# 05_NFC.net
KiCad netlist of a schematic drawn in Altium Designer
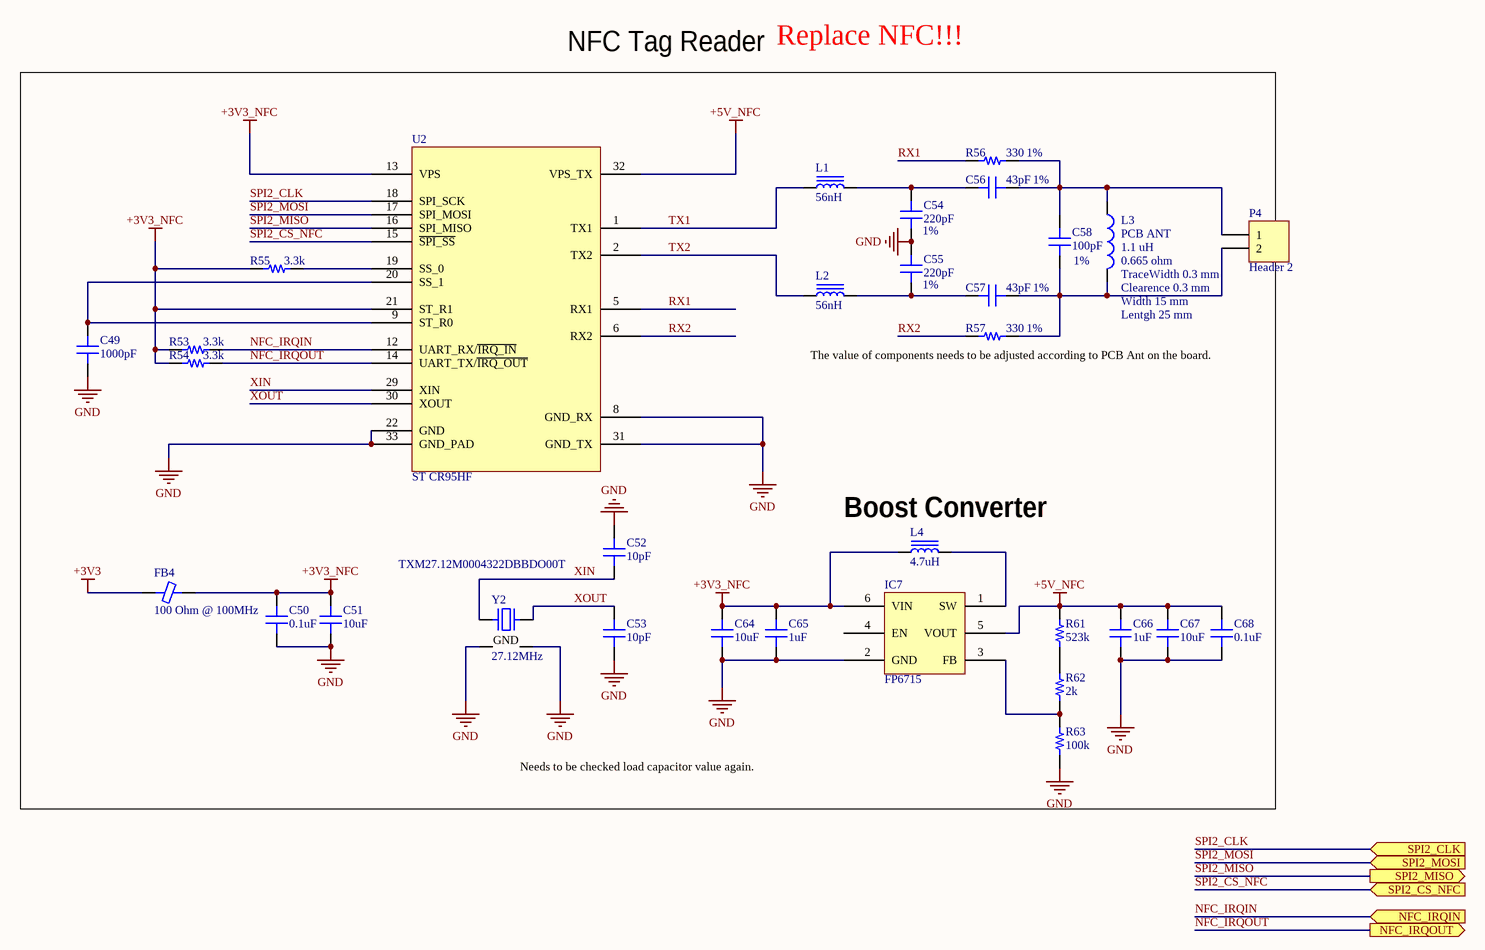
[diagram p0: [05] NFC.SchDoc]

(export (version "E")
  (design (tool "Eeschema 10.0.6"))
  (components
    (comp (ref "C49")
      (value "1000pF")
      (footprint "CAP 0402/1005")
      (description "CAP CER 1000PF 6.3V X7R 0402")
      (fields (field (name "PART NUMBER") "C0402C102K9RACTU") (field (name "MANUFACTURER") "Kemet"))
      (libsource (lib "Celestial Library Database") (part "Capacitor"))
    )
    (comp (ref "C50")
      (value "0.1uF")
      (footprint "CAP 0402/1005")
      (description "CAP CER 0.1UF 10V X7R 0402")
      (fields
        (field (name "PART NUMBER") "C1005X7R1A104K050BB")
        (field (name "MANUFACTURER") "TDK Corporation")
      )
      (libsource (lib "Celestial Library Database") (part "Capacitor"))
    )
    (comp (ref "C51")
      (value "10uF")
      (footprint "CAP 0603/1608")
      (description "CAP CER 10UF 10V X5R 0603")
      (fields
        (field (name "PART NUMBER") "C1608X5R1A106M080AC")
        (field (name "MANUFACTURER") "TDK Corporation")
      )
      (libsource (lib "Celestial Library Database") (part "Capacitor"))
    )
    (comp (ref "C52")
      (value "10pF")
      (footprint "CAP 0402/1005")
      (description "CAP CER 10PF 10V NP0 0402")
      (fields (field (name "PART NUMBER") "C0402C100C8GACTU") (field (name "MANUFACTURER") "Kemet"))
      (libsource (lib "Celestial Library Database") (part "Capacitor"))
    )
    (comp (ref "C53")
      (value "10pF")
      (footprint "CAP 0402/1005")
      (description "CAP CER 10PF 10V NP0 0402")
      (fields (field (name "PART NUMBER") "C0402C100C8GACTU") (field (name "MANUFACTURER") "Kemet"))
      (libsource (lib "Celestial Library Database") (part "Capacitor"))
    )
    (comp (ref "C54")
      (value "220pF")
      (footprint "CAP 0402/1005")
      (description "CAP CER 220PF 50V C0G 0402")
      (fields
        (field (name "PART NUMBER") "C1005C0G1H221F050BA")
        (field (name "MANUFACTURER") "TDK Corporation")
        (field (name "TOLERANCE") "1%")
      )
      (libsource (lib "Celestial Library Database") (part "Capacitor"))
    )
    (comp (ref "C55")
      (value "220pF")
      (footprint "CAP 0402/1005")
      (description "CAP CER 220PF 50V C0G 0402")
      (fields
        (field (name "PART NUMBER") "C1005C0G1H221F050BA")
        (field (name "MANUFACTURER") "TDK Corporation")
        (field (name "TOLERANCE") "1%")
      )
      (libsource (lib "Celestial Library Database") (part "Capacitor"))
    )
    (comp (ref "C56")
      (value "43pF")
      (footprint "CAP 0402/1005")
      (description "CAP CER 43PF 50V NP0 0402")
      (fields
        (field (name "PART NUMBER") "GRM1555C1H430GA01D")
        (field (name "MANUFACTURER") "Murata Electronics North America")
        (field (name "TOLERANCE") "1%")
      )
      (libsource (lib "Celestial Library Database") (part "Capacitor"))
    )
    (comp (ref "C57")
      (value "43pF")
      (footprint "CAP 0402/1005")
      (description "CAP CER 43PF 50V NP0 0402")
      (fields
        (field (name "PART NUMBER") "GRM1555C1H430GA01D")
        (field (name "MANUFACTURER") "Murata Electronics North America")
        (field (name "TOLERANCE") "1%")
      )
      (libsource (lib "Celestial Library Database") (part "Capacitor"))
    )
    (comp (ref "C58")
      (value "100pF")
      (footprint "CAP 0402/1005")
      (description "CAP CER 100PF 50V C0G 0402")
      (fields
        (field (name "PART NUMBER") "C1005C0G1H101F050BA")
        (field (name "MANUFACTURER") "TDK Corporation")
        (field (name "TOLERANCE") "1%")
      )
      (libsource (lib "Celestial Library Database") (part "Capacitor"))
    )
    (comp (ref "C64")
      (value "10uF")
      (footprint "CAP 0603/1608")
      (description "CAP CER 10UF 10V X5R 0603")
      (fields
        (field (name "PART NUMBER") "C1608X5R1A106K080AC")
        (field (name "MANUFACTURER") "TDK Corporation")
      )
      (libsource (lib "Celestial Library Database") (part "Capacitor"))
    )
    (comp (ref "C65")
      (value "1uF")
      (footprint "CAP 0603/1608")
      (description "CAP CER 1UF 25V X7R 0603")
      (fields (field (name "PART NUMBER") "C0603C105K3RACTU") (field (name "MANUFACTURER") "Kemet"))
      (libsource (lib "Celestial Library Database") (part "Capacitor"))
    )
    (comp (ref "C66")
      (value "1uF")
      (footprint "CAP 0603/1608")
      (description "CAP CER 1UF 25V X7R 0603")
      (fields (field (name "PART NUMBER") "C0603C105K3RACTU") (field (name "MANUFACTURER") "Kemet"))
      (libsource (lib "Celestial Library Database") (part "Capacitor"))
    )
    (comp (ref "C67")
      (value "10uF")
      (footprint "CAP 0603/1608")
      (description "CAP CER 10UF 10V X5R 0603")
      (fields
        (field (name "PART NUMBER") "C1608X5R1A106M080AC")
        (field (name "MANUFACTURER") "TDK Corporation")
      )
      (libsource (lib "Celestial Library Database") (part "Capacitor"))
    )
    (comp (ref "C68")
      (value "0.1uF")
      (footprint "CAP 0402/1005")
      (description "CAP CER 0.1UF 10V X7R 0402")
      (fields
        (field (name "PART NUMBER") "C1005X7R1A104K050BB")
        (field (name "MANUFACTURER") "TDK Corporation")
      )
      (libsource (lib "Celestial Library Database") (part "Capacitor"))
    )
    (comp (ref "FB4")
      (value "100 Ohm @ 100MHz")
      (footprint "FER 0603/1608")
      (description "FERRITE CHIP 100 OHM 0603")
      (fields (field (name "PART NUMBER") "BKP1608HS101-T") (field (name "MANUFACTURER") "Taiyo Yuden"))
      (libsource (lib "Celestial Library Database") (part "Ferrite Chip"))
    )
    (comp (ref "IC7")
      (value "FP6715")
      (footprint "Leaded:ATMEL SOT-23-6 6ST1")
      (description "550KHz High Efficiency Low Ripple Synchronous Step-Up Converter")
      (libsource (lib "Altium Component") (part "FP6715"))
    )
    (comp (ref "L1")
      (value "56nH")
      (footprint "IND 0402/1005 RF WW")
      (description "FIXED IND 56NH 200MA 1.17 OHM")
      (fields
        (field (name "PART NUMBER") "LQW15AN56NG00D")
        (field (name "MANUFACTURER") "Murata Electronics North America")
      )
      (libsource (lib "Celestial Library Database") (part "Inductor"))
    )
    (comp (ref "L2")
      (value "56nH")
      (footprint "IND 0402/1005 RF WW")
      (description "FIXED IND 56NH 200MA 1.17 OHM")
      (fields
        (field (name "PART NUMBER") "LQW15AN56NG00D")
        (field (name "MANUFACTURER") "Murata Electronics North America")
      )
      (libsource (lib "Celestial Library Database") (part "Inductor"))
    )
    (comp (ref "L3")
      (value "PCB ANT")
      (footprint "0402-A")
      (description "Inductor")
      (fields
        (field (name "L_ANT") "1.1 uH")
        (field (name "R_ANT") "0.665 ohm")
        (field (name "TRACEWIDTH") "TraceWidth 0.3 mm")
        (field (name "CLEARENCE") "Clearence 0.3 mm")
        (field (name "WIDTH") "Width 15 mm")
        (field (name "LENGTH") "Lentgh 25 mm")
        (field (name "PUBLISHER") "Altium Limited")
      )
      (libsource (lib "Miscellaneous Devices") (part "Inductor"))
    )
    (comp (ref "L4")
      (value "4.7uH")
      (footprint "TDK SPM3012")
      (description "FIXED IND 4.7UH 1.3A 270 MOHM")
      (fields (field (name "PART NUMBER") "SPM3012T-4R7M") (field (name "MANUFACTURER") "TDK Corporation"))
      (libsource (lib "Celestial Library Database") (part "Inductor"))
    )
    (comp (ref "P4")
      (value "Header 2")
      (footprint "HDR1X2")
      (description "Header, 2-Pin")
      (fields (field (name "PUBLISHER") "Altium Limited"))
      (libsource (lib "Miscellaneous Connectors") (part "Header 2"))
    )
    (comp (ref "R53")
      (value "3.3k")
      (footprint "RES 0402/1005")
      (description "RES SMD 3.3K OHM 5% 1/16W 0402")
      (fields (field (name "PART NUMBER") "RC0402JR-073K3L") (field (name "MANUFACTURER") "Yageo"))
      (libsource (lib "Celestial Library Database") (part "Resistor"))
    )
    (comp (ref "R54")
      (value "3.3k")
      (footprint "RES 0402/1005")
      (description "RES SMD 3.3K OHM 5% 1/16W 0402")
      (fields (field (name "PART NUMBER") "RC0402JR-073K3L") (field (name "MANUFACTURER") "Yageo"))
      (libsource (lib "Celestial Library Database") (part "Resistor"))
    )
    (comp (ref "R55")
      (value "3.3k")
      (footprint "RES 0402/1005")
      (description "RES SMD 3.3K OHM 5% 1/16W 0402")
      (fields (field (name "PART NUMBER") "RC0402JR-073K3L") (field (name "MANUFACTURER") "Yageo"))
      (libsource (lib "Celestial Library Database") (part "Resistor"))
    )
    (comp (ref "R56")
      (value "330")
      (footprint "RES 0402/1005")
      (description "RES SMD 330 OHM 1% 1/10W 0402")
      (fields
        (field (name "PART NUMBER") "ERJ-2RKF3300X")
        (field (name "MANUFACTURER") "Panasonic Electronic Components")
        (field (name "TOLERANCE") "1%")
      )
      (libsource (lib "Celestial Library Database") (part "Resistor"))
    )
    (comp (ref "R57")
      (value "330")
      (footprint "RES 0402/1005")
      (description "RES SMD 330 OHM 1% 1/10W 0402")
      (fields
        (field (name "PART NUMBER") "ERJ-2RKF3300X")
        (field (name "MANUFACTURER") "Panasonic Electronic Components")
        (field (name "TOLERANCE") "1%")
      )
      (libsource (lib "Celestial Library Database") (part "Resistor"))
    )
    (comp (ref "R61")
      (value "523k")
      (footprint "RES 0402/1005")
      (description "RES SMD 523K OHM 1% 1/10W 0402")
      (fields
        (field (name "PART NUMBER") "ERJ-2RKF5233X")
        (field (name "MANUFACTURER") "Panasonic Electronic Components")
      )
      (libsource (lib "Celestial Library Database") (part "Resistor"))
    )
    (comp (ref "R62")
      (value "2k")
      (footprint "RES 0402/1005")
      (description "RES SMD 2K OHM 5% 1/10W 0402")
      (fields
        (field (name "PART NUMBER") "ERJ-2GEJ202X")
        (field (name "MANUFACTURER") "Panasonic Electronic Components")
      )
      (libsource (lib "Celestial Library Database") (part "Resistor"))
    )
    (comp (ref "R63")
      (value "100k")
      (footprint "RES 0402/1005")
      (description "RES SMD 100K OHM 1% 1/10W 0402")
      (fields
        (field (name "PART NUMBER") "ERJ-2RKF1003X")
        (field (name "MANUFACTURER") "Panasonic Electronic Components")
      )
      (libsource (lib "Celestial Library Database") (part "Resistor"))
    )
    (comp (ref "U2")
      (value "ST CR95HF")
      (footprint "Leadless:ST VFQFPN-32")
      (libsource (lib "Altium Component") (part "ST CR95HF"))
    )
    (comp (ref "Y2")
      (value "27.12MHz")
      (footprint "NDK NX3225SA")
      (description "CRYSTAL 27.1200MHZ 8PF SMD")
      (fields (field (name "PART NUMBER") "TXM27.12M0004322DBBDO00T") (field (name "MANUFACTURER") "NDK"))
      (libsource (lib "Celestial Library Database") (part "NDK Crystal NX3225SA"))
    )
  )
  (nets
    (net (code "1") (name "+3V3") (class "Default")
      (node (ref "FB4") (pin "1") (pinfunction "1_1") (pintype "passive"))
    )
    (net (code "2") (name "+3V3_NFC") (class "Default")
      (node (ref "C50") (pin "2") (pinfunction "2_2") (pintype "passive"))
      (node (ref "C51") (pin "2") (pinfunction "2_2") (pintype "passive"))
      (node (ref "C64") (pin "2") (pinfunction "2_2") (pintype "passive"))
      (node (ref "C65") (pin "2") (pinfunction "2_2") (pintype "passive"))
      (node (ref "FB4") (pin "2") (pinfunction "2_2") (pintype "passive"))
      (node (ref "IC7") (pin "6") (pinfunction "VIN_6") (pintype "passive"))
      (node (ref "L4") (pin "1") (pinfunction "1_1") (pintype "passive"))
      (node (ref "R53") (pin "1") (pinfunction "1_1") (pintype "passive"))
      (node (ref "R54") (pin "1") (pinfunction "1_1") (pintype "passive"))
      (node (ref "R55") (pin "1") (pinfunction "1_1") (pintype "passive"))
      (node (ref "U2") (pin "13") (pinfunction "VPS_13") (pintype "passive"))
      (node (ref "U2") (pin "21") (pinfunction "ST_R1_21") (pintype "passive"))
    )
    (net (code "3") (name "+5V_NFC") (class "Default")
      (node (ref "C66") (pin "2") (pinfunction "2_2") (pintype "passive"))
      (node (ref "C67") (pin "2") (pinfunction "2_2") (pintype "passive"))
      (node (ref "C68") (pin "2") (pinfunction "2_2") (pintype "passive"))
      (node (ref "IC7") (pin "5") (pinfunction "VOUT_5") (pintype "passive"))
      (node (ref "R61") (pin "2") (pinfunction "2_2") (pintype "passive"))
      (node (ref "U2") (pin "32") (pinfunction "VPS_TX_32") (pintype "passive"))
    )
    (net (code "4") (name "/NFC_IRQIN") (class "Default")
      (node (ref "R53") (pin "2") (pinfunction "2_2") (pintype "passive"))
      (node (ref "U2") (pin "12") (pinfunction "UART_RX/~{IRQ_IN}_12") (pintype "passive"))
    )
    (net (code "5") (name "/NFC_IRQOUT") (class "Default")
      (node (ref "R54") (pin "2") (pinfunction "2_2") (pintype "passive"))
      (node (ref "U2") (pin "14") (pinfunction "UART_TX/~{IRQ_OUT}_14") (pintype "passive"))
    )
    (net (code "6") (name "/RX1") (class "Default")
      (node (ref "R56") (pin "1") (pinfunction "1_1") (pintype "passive"))
      (node (ref "U2") (pin "5") (pinfunction "RX1_5") (pintype "passive"))
    )
    (net (code "7") (name "/RX2") (class "Default")
      (node (ref "R57") (pin "1") (pinfunction "1_1") (pintype "passive"))
      (node (ref "U2") (pin "6") (pinfunction "RX2_6") (pintype "passive"))
    )
    (net (code "8") (name "/SPI2_CLK") (class "Default")
      (node (ref "U2") (pin "18") (pinfunction "SPI_SCK_18") (pintype "passive"))
    )
    (net (code "9") (name "/SPI2_CS_NFC") (class "Default")
      (node (ref "U2") (pin "15") (pinfunction "~{SPI_SS}_15") (pintype "passive"))
    )
    (net (code "10") (name "/SPI2_MISO") (class "Default")
      (node (ref "U2") (pin "16") (pinfunction "SPI_MISO_16") (pintype "passive"))
    )
    (net (code "11") (name "/SPI2_MOSI") (class "Default")
      (node (ref "U2") (pin "17") (pinfunction "SPI_MOSI_17") (pintype "passive"))
    )
    (net (code "12") (name "/TX1") (class "Default")
      (node (ref "L1") (pin "1") (pinfunction "1_1") (pintype "passive"))
      (node (ref "U2") (pin "1") (pinfunction "TX1_1") (pintype "passive"))
    )
    (net (code "13") (name "/TX2") (class "Default")
      (node (ref "L2") (pin "1") (pinfunction "1_1") (pintype "passive"))
      (node (ref "U2") (pin "2") (pinfunction "TX2_2") (pintype "passive"))
    )
    (net (code "14") (name "/XIN") (class "Default")
      (node (ref "C52") (pin "1") (pinfunction "1_1") (pintype "passive"))
      (node (ref "U2") (pin "29") (pinfunction "XIN_29") (pintype "passive"))
      (node (ref "Y2") (pin "1") (pinfunction "1_1") (pintype "passive"))
    )
    (net (code "15") (name "/XOUT") (class "Default")
      (node (ref "C53") (pin "2") (pinfunction "2_2") (pintype "passive"))
      (node (ref "U2") (pin "30") (pinfunction "XOUT_30") (pintype "passive"))
      (node (ref "Y2") (pin "3") (pinfunction "3_3") (pintype "passive"))
    )
    (net (code "16") (name "GND") (class "Default")
      (node (ref "C49") (pin "1") (pinfunction "1_1") (pintype "passive"))
      (node (ref "C50") (pin "1") (pinfunction "1_1") (pintype "passive"))
      (node (ref "C51") (pin "1") (pinfunction "1_1") (pintype "passive"))
      (node (ref "C52") (pin "2") (pinfunction "2_2") (pintype "passive"))
      (node (ref "C53") (pin "1") (pinfunction "1_1") (pintype "passive"))
      (node (ref "C54") (pin "1") (pinfunction "1_1") (pintype "passive"))
      (node (ref "C55") (pin "2") (pinfunction "2_2") (pintype "passive"))
      (node (ref "C64") (pin "1") (pinfunction "1_1") (pintype "passive"))
      (node (ref "C65") (pin "1") (pinfunction "1_1") (pintype "passive"))
      (node (ref "C66") (pin "1") (pinfunction "1_1") (pintype "passive"))
      (node (ref "C67") (pin "1") (pinfunction "1_1") (pintype "passive"))
      (node (ref "C68") (pin "1") (pinfunction "1_1") (pintype "passive"))
      (node (ref "IC7") (pin "2") (pinfunction "GND_2") (pintype "passive"))
      (node (ref "R63") (pin "1") (pinfunction "1_1") (pintype "passive"))
      (node (ref "U2") (pin "22") (pinfunction "GND_22") (pintype "passive"))
      (node (ref "U2") (pin "31") (pinfunction "GND_TX_31") (pintype "passive"))
      (node (ref "U2") (pin "33") (pinfunction "GND_PAD_33") (pintype "passive"))
      (node (ref "U2") (pin "8") (pinfunction "GND_RX_8") (pintype "passive"))
      (node (ref "Y2") (pin "2") (pinfunction "GND_2") (pintype "passive"))
      (node (ref "Y2") (pin "4") (pinfunction "GND_4") (pintype "passive"))
    )
    (net (code "17") (name "Net-(C54-Pad2)") (class "Default")
      (node (ref "C54") (pin "2") (pinfunction "2_2") (pintype "passive"))
      (node (ref "C56") (pin "1") (pinfunction "1_1") (pintype "passive"))
      (node (ref "L1") (pin "2") (pinfunction "2_2") (pintype "passive"))
    )
    (net (code "18") (name "Net-(C55-Pad1)") (class "Default")
      (node (ref "C55") (pin "1") (pinfunction "1_1") (pintype "passive"))
      (node (ref "C57") (pin "1") (pinfunction "1_1") (pintype "passive"))
      (node (ref "L2") (pin "2") (pinfunction "2_2") (pintype "passive"))
    )
    (net (code "19") (name "Net-(C56-Pad2)") (class "Default")
      (node (ref "C56") (pin "2") (pinfunction "2_2") (pintype "passive"))
      (node (ref "C58") (pin "2") (pinfunction "2_2") (pintype "passive"))
      (node (ref "L3") (pin "1") (pinfunction "1_1") (pintype "passive"))
      (node (ref "P4") (pin "1") (pinfunction "1_1") (pintype "passive"))
      (node (ref "R56") (pin "2") (pinfunction "2_2") (pintype "passive"))
    )
    (net (code "20") (name "Net-(C57-Pad2)") (class "Default")
      (node (ref "C57") (pin "2") (pinfunction "2_2") (pintype "passive"))
      (node (ref "C58") (pin "1") (pinfunction "1_1") (pintype "passive"))
      (node (ref "L3") (pin "2") (pinfunction "2_2") (pintype "passive"))
      (node (ref "P4") (pin "2") (pinfunction "2_2") (pintype "passive"))
      (node (ref "R57") (pin "2") (pinfunction "2_2") (pintype "passive"))
    )
    (net (code "21") (name "Net-(IC7-FB)") (class "Default")
      (node (ref "IC7") (pin "3") (pinfunction "FB_3") (pintype "passive"))
      (node (ref "R62") (pin "1") (pinfunction "1_1") (pintype "passive"))
      (node (ref "R63") (pin "2") (pinfunction "2_2") (pintype "passive"))
    )
    (net (code "22") (name "Net-(IC7-SW)") (class "Default")
      (node (ref "IC7") (pin "1") (pinfunction "SW_1") (pintype "passive"))
      (node (ref "L4") (pin "2") (pinfunction "2_2") (pintype "passive"))
    )
    (net (code "23") (name "Net-(R61-Pad1)") (class "Default")
      (node (ref "R61") (pin "1") (pinfunction "1_1") (pintype "passive"))
      (node (ref "R62") (pin "2") (pinfunction "2_2") (pintype "passive"))
    )
    (net (code "24") (name "Net-(U2-SS_0)") (class "Default")
      (node (ref "R55") (pin "2") (pinfunction "2_2") (pintype "passive"))
      (node (ref "U2") (pin "19") (pinfunction "SS_0_19") (pintype "passive"))
    )
    (net (code "25") (name "Net-(U2-SS_1)") (class "Default")
      (node (ref "C49") (pin "2") (pinfunction "2_2") (pintype "passive"))
      (node (ref "U2") (pin "20") (pinfunction "SS_1_20") (pintype "passive"))
      (node (ref "U2") (pin "9") (pinfunction "ST_R0_9") (pintype "passive"))
    )
    (net (code "26") (name "unconnected-(IC7-EN-Pad4)") (class "Default")
      (node (ref "IC7") (pin "4") (pinfunction "EN_4") (pintype "passive"))
    )
    (net (code "27") (name "unconnected-(U2-NC-Pad3)") (class "Default")
      (node (ref "U2") (pin "3") (pinfunction "NC_3") (pintype "passive"))
    )
    (net (code "28") (name "unconnected-(U2-NC-Pad4)") (class "Default")
      (node (ref "U2") (pin "4") (pinfunction "NC_4") (pintype "passive"))
    )
    (net (code "29") (name "unconnected-(U2-NC-Pad7)") (class "Default")
      (node (ref "U2") (pin "7") (pinfunction "NC_7") (pintype "passive"))
    )
    (net (code "30") (name "unconnected-(U2-NC-Pad10)") (class "Default")
      (node (ref "U2") (pin "10") (pinfunction "NC_10") (pintype "passive"))
    )
    (net (code "31") (name "unconnected-(U2-NC-Pad11)") (class "Default")
      (node (ref "U2") (pin "11") (pinfunction "NC_11") (pintype "passive"))
    )
    (net (code "32") (name "unconnected-(U2-NC-Pad23)") (class "Default")
      (node (ref "U2") (pin "23") (pinfunction "NC_23") (pintype "passive"))
    )
    (net (code "33") (name "unconnected-(U2-NC-Pad24)") (class "Default")
      (node (ref "U2") (pin "24") (pinfunction "NC_24") (pintype "passive"))
    )
    (net (code "34") (name "unconnected-(U2-NC-Pad25)") (class "Default")
      (node (ref "U2") (pin "25") (pinfunction "NC_25") (pintype "passive"))
    )
    (net (code "35") (name "unconnected-(U2-NC-Pad26)") (class "Default")
      (node (ref "U2") (pin "26") (pinfunction "NC_26") (pintype "passive"))
    )
    (net (code "36") (name "unconnected-(U2-NC-Pad27)") (class "Default")
      (node (ref "U2") (pin "27") (pinfunction "NC_27") (pintype "passive"))
    )
    (net (code "37") (name "unconnected-(U2-NC-Pad28)") (class "Default")
      (node (ref "U2") (pin "28") (pinfunction "NC_28") (pintype "passive"))
    )
  )
)
